# CO_Output_Processing.net
KiCad netlist of a schematic drawn in Altium Designer
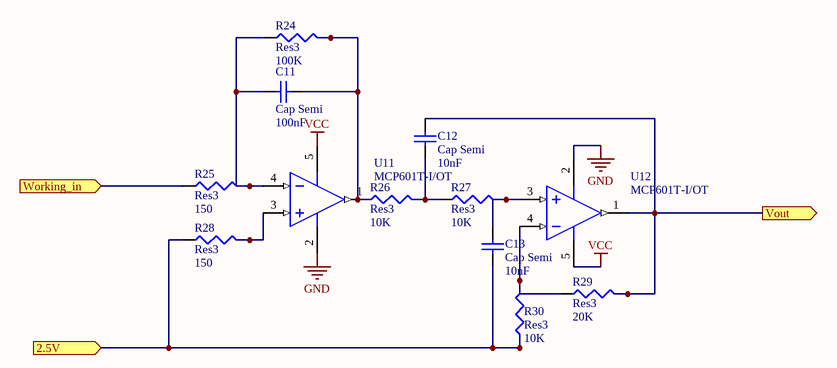
[diagram p0: CO_Output_Processing.SchDoc]

(export (version "E")
  (design (tool "Eeschema 10.0.6"))
  (components
    (comp (ref "C11")
      (value "Cap Semi")
      (footprint "C1206")
      (description "Capacitor (Semiconductor SIM Model)")
      (fields (field (name "ALTIUM_VALUE") "100nF") (field (name "PUBLISHER") "Altium Limited"))
      (libsource (lib "Miscellaneous Devices") (part "Cap Semi"))
    )
    (comp (ref "C12")
      (value "Cap Semi")
      (footprint "C1206")
      (description "Capacitor (Semiconductor SIM Model)")
      (fields (field (name "ALTIUM_VALUE") "10nF") (field (name "PUBLISHER") "Altium Limited"))
      (libsource (lib "Miscellaneous Devices") (part "Cap Semi"))
    )
    (comp (ref "C13")
      (value "Cap Semi")
      (footprint "C1206")
      (description "Capacitor (Semiconductor SIM Model)")
      (fields (field (name "ALTIUM_VALUE") "10nF") (field (name "PUBLISHER") "Altium Limited"))
      (libsource (lib "Miscellaneous Devices") (part "Cap Semi"))
    )
    (comp (ref "R24")
      (value "Res3")
      (footprint "J1-0603")
      (description "Resistor")
      (fields (field (name "ALTIUM_VALUE") "100K") (field (name "PUBLISHER") "Altium Limited"))
      (libsource (lib "Miscellaneous Devices") (part "Res3"))
    )
    (comp (ref "R25")
      (value "Res3")
      (footprint "J1-0603")
      (description "Resistor")
      (fields (field (name "ALTIUM_VALUE") "150") (field (name "PUBLISHER") "Altium Limited"))
      (libsource (lib "Miscellaneous Devices") (part "Res3"))
    )
    (comp (ref "R26")
      (value "Res3")
      (footprint "J1-0603")
      (description "Resistor")
      (fields (field (name "ALTIUM_VALUE") "10K") (field (name "PUBLISHER") "Altium Limited"))
      (libsource (lib "Miscellaneous Devices") (part "Res3"))
    )
    (comp (ref "R27")
      (value "Res3")
      (footprint "J1-0603")
      (description "Resistor")
      (fields (field (name "ALTIUM_VALUE") "10K") (field (name "PUBLISHER") "Altium Limited"))
      (libsource (lib "Miscellaneous Devices") (part "Res3"))
    )
    (comp (ref "R28")
      (value "Res3")
      (footprint "J1-0603")
      (description "Resistor")
      (fields (field (name "ALTIUM_VALUE") "150") (field (name "PUBLISHER") "Altium Limited"))
      (libsource (lib "Miscellaneous Devices") (part "Res3"))
    )
    (comp (ref "R29")
      (value "Res3")
      (footprint "J1-0603")
      (description "Resistor")
      (fields (field (name "ALTIUM_VALUE") "20K") (field (name "PUBLISHER") "Altium Limited"))
      (libsource (lib "Miscellaneous Devices") (part "Res3"))
    )
    (comp (ref "R30")
      (value "Res3")
      (footprint "J1-0603")
      (description "Resistor")
      (fields (field (name "ALTIUM_VALUE") "10K") (field (name "PUBLISHER") "Altium Limited"))
      (libsource (lib "Miscellaneous Devices") (part "Res3"))
    )
    (comp (ref "U11")
      (value "MCP601T-I/OT")
      (footprint "SOT-23-OT5_L")
      (libsource (lib "Altium Content Vault") (part "AMP-OPA-MCP601-SOT5"))
    )
    (comp (ref "U12")
      (value "MCP601T-I/OT")
      (footprint "SOT-23-OT5_L")
      (libsource (lib "Altium Content Vault") (part "AMP-OPA-MCP601-SOT5"))
    )
  )
  (nets
    (net (code "1") (name "/2.5V") (class "Default")
      (node (ref "C13") (pin "1") (pinfunction "1_1") (pintype "passive"))
      (node (ref "R28") (pin "1") (pinfunction "1_1") (pintype "passive"))
      (node (ref "R30") (pin "1") (pinfunction "1_1") (pintype "passive"))
    )
    (net (code "2") (name "/Vout") (class "Default")
      (node (ref "C12") (pin "2") (pinfunction "2_2") (pintype "passive"))
      (node (ref "R29") (pin "2") (pinfunction "2_2") (pintype "passive"))
      (node (ref "U12") (pin "1") (pinfunction "VOUT_1") (pintype "output"))
    )
    (net (code "3") (name "/Working_in") (class "Default")
      (node (ref "R25") (pin "1") (pinfunction "1_1") (pintype "passive"))
    )
    (net (code "4") (name "GND") (class "Default")
      (node (ref "U11") (pin "2") (pinfunction "VSS_2") (pintype "power_in"))
      (node (ref "U12") (pin "2") (pinfunction "VSS_2") (pintype "power_in"))
    )
    (net (code "5") (name "Net-(C12-Pad1)") (class "Default")
      (node (ref "C12") (pin "1") (pinfunction "1_1") (pintype "passive"))
      (node (ref "R26") (pin "2") (pinfunction "2_2") (pintype "passive"))
      (node (ref "R27") (pin "1") (pinfunction "1_1") (pintype "passive"))
    )
    (net (code "6") (name "Net-(U11-VIN+)") (class "Default")
      (node (ref "R28") (pin "2") (pinfunction "2_2") (pintype "passive"))
      (node (ref "U11") (pin "3") (pinfunction "VIN+_3") (pintype "input"))
    )
    (net (code "7") (name "Net-(U11-VIN-)") (class "Default")
      (node (ref "C11") (pin "1") (pinfunction "1_1") (pintype "passive"))
      (node (ref "R24") (pin "1") (pinfunction "1_1") (pintype "passive"))
      (node (ref "R25") (pin "2") (pinfunction "2_2") (pintype "passive"))
      (node (ref "U11") (pin "4") (pinfunction "VIN-_4") (pintype "input"))
    )
    (net (code "8") (name "Net-(U11-VOUT)") (class "Default")
      (node (ref "C11") (pin "2") (pinfunction "2_2") (pintype "passive"))
      (node (ref "R24") (pin "2") (pinfunction "2_2") (pintype "passive"))
      (node (ref "R26") (pin "1") (pinfunction "1_1") (pintype "passive"))
      (node (ref "U11") (pin "1") (pinfunction "VOUT_1") (pintype "output"))
    )
    (net (code "9") (name "Net-(U12-VIN+)") (class "Default")
      (node (ref "C13") (pin "2") (pinfunction "2_2") (pintype "passive"))
      (node (ref "R27") (pin "2") (pinfunction "2_2") (pintype "passive"))
      (node (ref "U12") (pin "3") (pinfunction "VIN+_3") (pintype "input"))
    )
    (net (code "10") (name "Net-(U12-VIN-)") (class "Default")
      (node (ref "R29") (pin "1") (pinfunction "1_1") (pintype "passive"))
      (node (ref "R30") (pin "2") (pinfunction "2_2") (pintype "passive"))
      (node (ref "U12") (pin "4") (pinfunction "VIN-_4") (pintype "input"))
    )
    (net (code "11") (name "VCC") (class "Default")
      (node (ref "U11") (pin "5") (pinfunction "VDD_5") (pintype "power_in"))
      (node (ref "U12") (pin "5") (pinfunction "VDD_5") (pintype "power_in"))
    )
  )
)
